# Rev_B.net
KiCad netlist of a schematic drawn in EAGLE
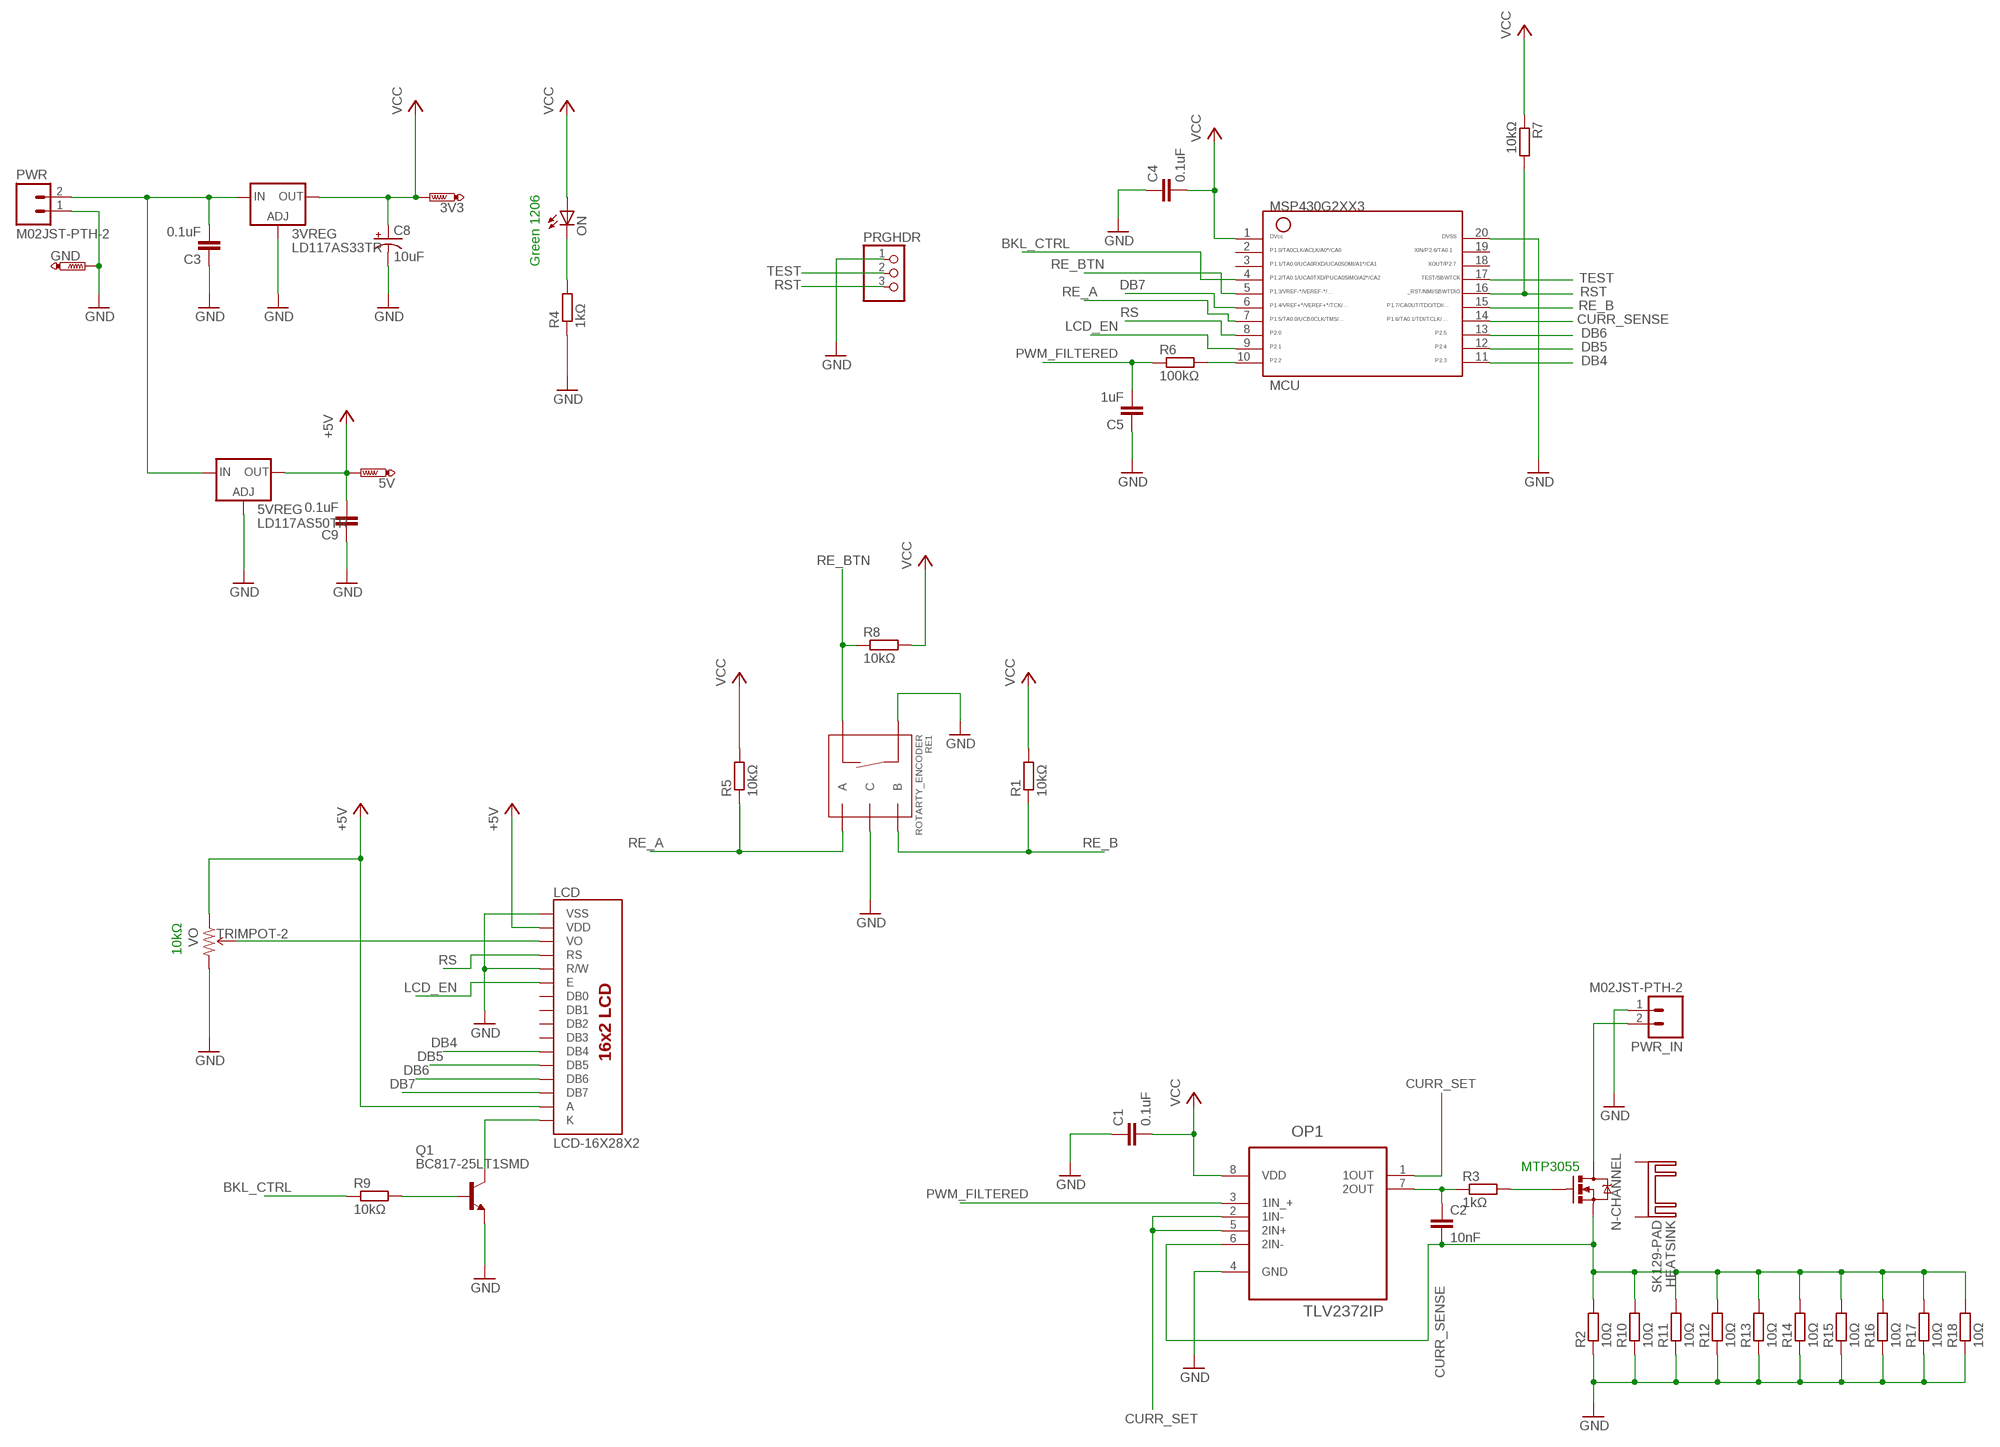
[diagram p0: schematic, sheet 1]

(export (version "E")
  (design (tool "Eeschema 10.0.6"))
  (components
    (comp (ref "3V3")
      (value "PTR1TP10SQ")
      (footprint "eagle-import:TP10SQ")
      (libsource (lib "eagle-import") (part "PTR1TP10SQ"))
    )
    (comp (ref "3VREG")
      (value "LD117AS33TR")
      (footprint "eagle-import:SOT223")
      (libsource (lib "eagle-import") (part "LD117A?S33TR"))
    )
    (comp (ref "5V")
      (value "PTR1TP10SQ")
      (footprint "eagle-import:TP10SQ")
      (libsource (lib "eagle-import") (part "PTR1TP10SQ"))
    )
    (comp (ref "5VREG")
      (value "LD117AS50TR")
      (footprint "eagle-import:SOT223")
      (libsource (lib "eagle-import") (part "LD117A?S50TR"))
    )
    (comp (ref "C1")
      (value "0.1uF")
      (footprint "eagle-import:C0805")
      (libsource (lib "eagle-import") (part "C-EUC0805"))
    )
    (comp (ref "C2")
      (value "10nF")
      (footprint "eagle-import:C0805")
      (libsource (lib "eagle-import") (part "C-EUC0805"))
    )
    (comp (ref "C3")
      (value "0.1uF")
      (footprint "eagle-import:C0805")
      (libsource (lib "eagle-import") (part "C-EUC0805"))
    )
    (comp (ref "C4")
      (value "0.1uF")
      (footprint "eagle-import:C0805")
      (libsource (lib "eagle-import") (part "C-EUC0805"))
    )
    (comp (ref "C5")
      (value "1uF")
      (footprint "eagle-import:C0805")
      (libsource (lib "eagle-import") (part "C-EUC0805"))
    )
    (comp (ref "C8")
      (value "10uF")
      (footprint "eagle-import:EIA3216")
      (libsource (lib "eagle-import") (part "CAP_POL1206"))
    )
    (comp (ref "C9")
      (value "0.1uF")
      (footprint "eagle-import:C0805")
      (libsource (lib "eagle-import") (part "C-EUC0805"))
    )
    (comp (ref "GND")
      (value "PTR1TP10SQ")
      (footprint "eagle-import:TP10SQ")
      (libsource (lib "eagle-import") (part "PTR1TP10SQ"))
    )
    (comp (ref "HEATSINK")
      (value "SK129-PAD")
      (footprint "eagle-import:SK129")
      (libsource (lib "eagle-import") (part "SK129-PAD"))
    )
    (comp (ref "LCD")
      (value "LCD-16X28X2")
      (footprint "eagle-import:LCD-8X2")
      (libsource (lib "eagle-import") (part "LCD-16X28X2"))
    )
    (comp (ref "MCU")
      (value "G2XX3---N20")
      (footprint "eagle-import:N20")
      (libsource (lib "eagle-import") (part "G2XX3---N20"))
    )
    (comp (ref "N-CHANNEL")
      (value "MOSFET-NCHANNELFQP30N06L")
      (footprint "eagle-import:TO220V")
      (libsource (lib "eagle-import") (part "MOSFET-NCHANNELFQP30N06L"))
    )
    (comp (ref "ON")
      (value "LEDCHIPLED_1206")
      (footprint "eagle-import:CHIPLED_1206")
      (libsource (lib "eagle-import") (part "LEDCHIPLED_1206"))
    )
    (comp (ref "OP1")
      (value "TLV2372IP")
      (footprint "eagle-import:DIP254P762X508-8")
      (libsource (lib "eagle-import") (part "TLV2372IP"))
    )
    (comp (ref "PRGHDR")
      (value "PINHD-1X3")
      (footprint "eagle-import:1X03")
      (libsource (lib "eagle-import") (part "PINHD-1X3"))
    )
    (comp (ref "PWR")
      (value "M02JST-PTH-2")
      (footprint "eagle-import:JST-2-PTH")
      (libsource (lib "eagle-import") (part "M02JST-PTH-2"))
    )
    (comp (ref "PWR_IN")
      (value "M02JST-PTH-2")
      (footprint "eagle-import:JST-2-PTH")
      (libsource (lib "eagle-import") (part "M02JST-PTH-2"))
    )
    (comp (ref "Q1")
      (value "BC817-25LT1SMD")
      (footprint "eagle-import:SOT23-BEC")
      (libsource (lib "eagle-import") (part "BC817SMD-25LT1"))
    )
    (comp (ref "R1")
      (value "10kΩ")
      (footprint "eagle-import:R0805")
      (libsource (lib "eagle-import") (part "R-EU_R0805"))
    )
    (comp (ref "R2")
      (value "10Ω")
      (footprint "eagle-import:R2512")
      (libsource (lib "eagle-import") (part "R-EU_R2512"))
    )
    (comp (ref "R3")
      (value "1kΩ")
      (footprint "eagle-import:R0805")
      (libsource (lib "eagle-import") (part "R-EU_R0805"))
    )
    (comp (ref "R4")
      (value "1kΩ")
      (footprint "eagle-import:R0805")
      (libsource (lib "eagle-import") (part "R-EU_R0805"))
    )
    (comp (ref "R5")
      (value "10kΩ")
      (footprint "eagle-import:R0805")
      (libsource (lib "eagle-import") (part "R-EU_R0805"))
    )
    (comp (ref "R6")
      (value "100kΩ")
      (footprint "eagle-import:R0805")
      (libsource (lib "eagle-import") (part "R-EU_R0805"))
    )
    (comp (ref "R7")
      (value "10kΩ")
      (footprint "eagle-import:R0805")
      (libsource (lib "eagle-import") (part "resistor_R-EU_R0805"))
    )
    (comp (ref "R8")
      (value "10kΩ")
      (footprint "eagle-import:R0805")
      (libsource (lib "eagle-import") (part "R-EU_R0805"))
    )
    (comp (ref "R9")
      (value "10kΩ")
      (footprint "eagle-import:R0805")
      (libsource (lib "eagle-import") (part "R-EU_R0805"))
    )
    (comp (ref "R10")
      (value "10Ω")
      (footprint "eagle-import:R2512")
      (libsource (lib "eagle-import") (part "R-EU_R2512"))
    )
    (comp (ref "R11")
      (value "10Ω")
      (footprint "eagle-import:R2512")
      (libsource (lib "eagle-import") (part "R-EU_R2512"))
    )
    (comp (ref "R12")
      (value "10Ω")
      (footprint "eagle-import:R2512")
      (libsource (lib "eagle-import") (part "R-EU_R2512"))
    )
    (comp (ref "R13")
      (value "10Ω")
      (footprint "eagle-import:R2512")
      (libsource (lib "eagle-import") (part "R-EU_R2512"))
    )
    (comp (ref "R14")
      (value "10Ω")
      (footprint "eagle-import:R2512")
      (libsource (lib "eagle-import") (part "R-EU_R2512"))
    )
    (comp (ref "R15")
      (value "10Ω")
      (footprint "eagle-import:R2512")
      (libsource (lib "eagle-import") (part "R-EU_R2512"))
    )
    (comp (ref "R16")
      (value "10Ω")
      (footprint "eagle-import:R2512")
      (libsource (lib "eagle-import") (part "R-EU_R2512"))
    )
    (comp (ref "R17")
      (value "10Ω")
      (footprint "eagle-import:R2512")
      (libsource (lib "eagle-import") (part "R-EU_R2512"))
    )
    (comp (ref "R18")
      (value "10Ω")
      (footprint "eagle-import:R2512")
      (libsource (lib "eagle-import") (part "R-EU_R2512"))
    )
    (comp (ref "RE1")
      (value "ROTARTY_ENCODER")
      (footprint "eagle-import:ROTARY_ENC_PLAIN")
      (libsource (lib "eagle-import") (part "ROTARTY_ENCODER"))
    )
    (comp (ref "VO")
      (value "TRIMPOT-2")
      (footprint "eagle-import:TRIMPOT_TC33")
      (libsource (lib "eagle-import") (part "TRIMPOT-2"))
    )
  )
  (nets
    (net (code "1") (name "+5V") (class "Default")
      (node (ref "5V") (pin "TP") (pinfunction "TP_TP") (pintype "input"))
      (node (ref "5VREG") (pin "4") (pinfunction "OUT_4") (pintype "passive"))
      (node (ref "C9") (pin "2") (pinfunction "2_2") (pintype "passive"))
      (node (ref "LCD") (pin "15") (pinfunction "A_15") (pintype "power_in"))
      (node (ref "LCD") (pin "2") (pinfunction "VDD_2") (pintype "power_in"))
      (node (ref "VO") (pin "1") (pinfunction "CCW_1") (pintype "passive"))
    )
    (net (code "2") (name "/BKL_CTRL") (class "Default")
      (node (ref "MCU") (pin "4") (pinfunction "4_4") (pintype "bidirectional"))
      (node (ref "R9") (pin "1") (pinfunction "1_1") (pintype "passive"))
    )
    (net (code "3") (name "/CURR_SENSE") (class "Default")
      (node (ref "C2") (pin "2") (pinfunction "2_2") (pintype "passive"))
      (node (ref "MCU") (pin "14") (pinfunction "14_14") (pintype "bidirectional"))
      (node (ref "N-CHANNEL") (pin "3") (pinfunction "S_3") (pintype "passive"))
      (node (ref "OP1") (pin "6") (pinfunction "2IN-_6") (pintype "input"))
      (node (ref "R10") (pin "2") (pinfunction "2_2") (pintype "passive"))
      (node (ref "R11") (pin "2") (pinfunction "2_2") (pintype "passive"))
      (node (ref "R12") (pin "2") (pinfunction "2_2") (pintype "passive"))
      (node (ref "R13") (pin "2") (pinfunction "2_2") (pintype "passive"))
      (node (ref "R14") (pin "2") (pinfunction "2_2") (pintype "passive"))
      (node (ref "R15") (pin "2") (pinfunction "2_2") (pintype "passive"))
      (node (ref "R16") (pin "2") (pinfunction "2_2") (pintype "passive"))
      (node (ref "R17") (pin "2") (pinfunction "2_2") (pintype "passive"))
      (node (ref "R18") (pin "2") (pinfunction "2_2") (pintype "passive"))
      (node (ref "R2") (pin "2") (pinfunction "2_2") (pintype "passive"))
    )
    (net (code "4") (name "/CURR_SET") (class "Default")
      (node (ref "OP1") (pin "1") (pinfunction "1OUT_1") (pintype "output"))
      (node (ref "OP1") (pin "2") (pinfunction "1IN-_2") (pintype "input"))
      (node (ref "OP1") (pin "5") (pinfunction "2IN+_5") (pintype "input"))
    )
    (net (code "5") (name "/DB4") (class "Default")
      (node (ref "LCD") (pin "11") (pinfunction "DB4_11") (pintype "bidirectional"))
      (node (ref "MCU") (pin "11") (pinfunction "11_11") (pintype "bidirectional"))
    )
    (net (code "6") (name "/DB5") (class "Default")
      (node (ref "LCD") (pin "12") (pinfunction "DB5_12") (pintype "bidirectional"))
      (node (ref "MCU") (pin "12") (pinfunction "12_12") (pintype "bidirectional"))
    )
    (net (code "7") (name "/DB6") (class "Default")
      (node (ref "LCD") (pin "13") (pinfunction "DB6_13") (pintype "bidirectional"))
      (node (ref "MCU") (pin "13") (pinfunction "13_13") (pintype "bidirectional"))
    )
    (net (code "8") (name "/DB7") (class "Default")
      (node (ref "LCD") (pin "14") (pinfunction "DB7_14") (pintype "bidirectional"))
      (node (ref "MCU") (pin "6") (pinfunction "6_6") (pintype "bidirectional"))
    )
    (net (code "9") (name "/LCD_EN") (class "Default")
      (node (ref "LCD") (pin "6") (pinfunction "E_6") (pintype "input"))
      (node (ref "MCU") (pin "9") (pinfunction "9_9") (pintype "bidirectional"))
    )
    (net (code "10") (name "/PWM_FILTERED") (class "Default")
      (node (ref "C5") (pin "2") (pinfunction "2_2") (pintype "passive"))
      (node (ref "OP1") (pin "3") (pinfunction "1IN_+_3") (pintype "input"))
      (node (ref "R6") (pin "1") (pinfunction "1_1") (pintype "passive"))
    )
    (net (code "11") (name "/RE_A") (class "Default")
      (node (ref "MCU") (pin "7") (pinfunction "7_7") (pintype "bidirectional"))
      (node (ref "R5") (pin "1") (pinfunction "1_1") (pintype "passive"))
      (node (ref "RE1") (pin "A") (pinfunction "A_A") (pintype "bidirectional"))
    )
    (net (code "12") (name "/RE_B") (class "Default")
      (node (ref "MCU") (pin "15") (pinfunction "15_15") (pintype "bidirectional"))
      (node (ref "R1") (pin "1") (pinfunction "1_1") (pintype "passive"))
      (node (ref "RE1") (pin "B") (pinfunction "B_B") (pintype "bidirectional"))
    )
    (net (code "13") (name "/RE_BTN") (class "Default")
      (node (ref "MCU") (pin "5") (pinfunction "5_5") (pintype "bidirectional"))
      (node (ref "R8") (pin "1") (pinfunction "1_1") (pintype "passive"))
      (node (ref "RE1") (pin "SW-") (pinfunction "SW-_SW-") (pintype "bidirectional"))
    )
    (net (code "14") (name "/RS") (class "Default")
      (node (ref "LCD") (pin "4") (pinfunction "RS_4") (pintype "input"))
      (node (ref "MCU") (pin "8") (pinfunction "8_8") (pintype "bidirectional"))
    )
    (net (code "15") (name "/RST") (class "Default")
      (node (ref "MCU") (pin "16") (pinfunction "16_16") (pintype "bidirectional"))
      (node (ref "PRGHDR") (pin "3") (pinfunction "3_3") (pintype "passive"))
      (node (ref "R7") (pin "2") (pinfunction "2_2") (pintype "passive"))
    )
    (net (code "16") (name "/TEST") (class "Default")
      (node (ref "MCU") (pin "17") (pinfunction "17_17") (pintype "bidirectional"))
      (node (ref "PRGHDR") (pin "2") (pinfunction "2_2") (pintype "passive"))
    )
    (net (code "17") (name "GND") (class "Default")
      (node (ref "3VREG") (pin "1") (pinfunction "ADJ_1") (pintype "input"))
      (node (ref "5VREG") (pin "1") (pinfunction "ADJ_1") (pintype "input"))
      (node (ref "C1") (pin "1") (pinfunction "1_1") (pintype "passive"))
      (node (ref "C3") (pin "1") (pinfunction "1_1") (pintype "passive"))
      (node (ref "C4") (pin "1") (pinfunction "1_1") (pintype "passive"))
      (node (ref "C5") (pin "1") (pinfunction "1_1") (pintype "passive"))
      (node (ref "C8") (pin "C") (pinfunction "-_C") (pintype "passive"))
      (node (ref "C9") (pin "1") (pinfunction "1_1") (pintype "passive"))
      (node (ref "GND") (pin "TP") (pinfunction "TP_TP") (pintype "input"))
      (node (ref "LCD") (pin "1") (pinfunction "VSS_1") (pintype "power_in"))
      (node (ref "LCD") (pin "5") (pinfunction "R/W_5") (pintype "input"))
      (node (ref "MCU") (pin "20") (pinfunction "20_20") (pintype "bidirectional"))
      (node (ref "OP1") (pin "4") (pinfunction "GND_4") (pintype "passive"))
      (node (ref "PRGHDR") (pin "1") (pinfunction "1_1") (pintype "passive"))
      (node (ref "PWR") (pin "1") (pinfunction "1_1") (pintype "passive"))
      (node (ref "PWR_IN") (pin "1") (pinfunction "1_1") (pintype "passive"))
      (node (ref "Q1") (pin "E") (pinfunction "E_E") (pintype "passive"))
      (node (ref "R10") (pin "1") (pinfunction "1_1") (pintype "passive"))
      (node (ref "R11") (pin "1") (pinfunction "1_1") (pintype "passive"))
      (node (ref "R12") (pin "1") (pinfunction "1_1") (pintype "passive"))
      (node (ref "R13") (pin "1") (pinfunction "1_1") (pintype "passive"))
      (node (ref "R14") (pin "1") (pinfunction "1_1") (pintype "passive"))
      (node (ref "R15") (pin "1") (pinfunction "1_1") (pintype "passive"))
      (node (ref "R16") (pin "1") (pinfunction "1_1") (pintype "passive"))
      (node (ref "R17") (pin "1") (pinfunction "1_1") (pintype "passive"))
      (node (ref "R18") (pin "1") (pinfunction "1_1") (pintype "passive"))
      (node (ref "R2") (pin "1") (pinfunction "1_1") (pintype "passive"))
      (node (ref "R4") (pin "1") (pinfunction "1_1") (pintype "passive"))
      (node (ref "RE1") (pin "C") (pinfunction "C_C") (pintype "bidirectional"))
      (node (ref "RE1") (pin "SW+") (pinfunction "SW+_SW+") (pintype "bidirectional"))
      (node (ref "VO") (pin "3") (pinfunction "CW_3") (pintype "passive"))
    )
    (net (code "18") (name "Net-(3VREG-IN)") (class "Default")
      (node (ref "3VREG") (pin "3") (pinfunction "IN_3") (pintype "input"))
      (node (ref "5VREG") (pin "3") (pinfunction "IN_3") (pintype "input"))
      (node (ref "C3") (pin "2") (pinfunction "2_2") (pintype "passive"))
      (node (ref "PWR") (pin "2") (pinfunction "2_2") (pintype "passive"))
    )
    (net (code "19") (name "Net-(LCD-K)") (class "Default")
      (node (ref "LCD") (pin "16") (pinfunction "K_16") (pintype "power_in"))
      (node (ref "Q1") (pin "C") (pinfunction "C_C") (pintype "passive"))
    )
    (net (code "20") (name "Net-(LCD-VO)") (class "Default")
      (node (ref "LCD") (pin "3") (pinfunction "VO_3") (pintype "bidirectional"))
      (node (ref "VO") (pin "2") (pinfunction "WIPER_2") (pintype "passive"))
    )
    (net (code "21") (name "Net-(MCU-Pad10)") (class "Default")
      (node (ref "MCU") (pin "10") (pinfunction "10_10") (pintype "bidirectional"))
      (node (ref "R6") (pin "2") (pinfunction "2_2") (pintype "passive"))
    )
    (net (code "22") (name "Net-(N-CHANNEL-D)") (class "Default")
      (node (ref "N-CHANNEL") (pin "2") (pinfunction "D_2") (pintype "passive"))
      (node (ref "PWR_IN") (pin "2") (pinfunction "2_2") (pintype "passive"))
    )
    (net (code "23") (name "Net-(N-CHANNEL-G)") (class "Default")
      (node (ref "N-CHANNEL") (pin "1") (pinfunction "G_1") (pintype "passive"))
      (node (ref "R3") (pin "2") (pinfunction "2_2") (pintype "passive"))
    )
    (net (code "24") (name "Net-(ON-PadC)") (class "Default")
      (node (ref "ON") (pin "C") (pinfunction "C_C") (pintype "passive"))
      (node (ref "R4") (pin "2") (pinfunction "2_2") (pintype "passive"))
    )
    (net (code "25") (name "Net-(OP1-2OUT)") (class "Default")
      (node (ref "C2") (pin "1") (pinfunction "1_1") (pintype "passive"))
      (node (ref "OP1") (pin "7") (pinfunction "2OUT_7") (pintype "output"))
      (node (ref "R3") (pin "1") (pinfunction "1_1") (pintype "passive"))
    )
    (net (code "26") (name "Net-(Q1-PadB)") (class "Default")
      (node (ref "Q1") (pin "B") (pinfunction "B_B") (pintype "passive"))
      (node (ref "R9") (pin "2") (pinfunction "2_2") (pintype "passive"))
    )
    (net (code "27") (name "VCC") (class "Default")
      (node (ref "3V3") (pin "TP") (pinfunction "TP_TP") (pintype "input"))
      (node (ref "3VREG") (pin "4") (pinfunction "OUT_4") (pintype "passive"))
      (node (ref "C1") (pin "2") (pinfunction "2_2") (pintype "passive"))
      (node (ref "C4") (pin "2") (pinfunction "2_2") (pintype "passive"))
      (node (ref "C8") (pin "A") (pinfunction "+_A") (pintype "passive"))
      (node (ref "MCU") (pin "1") (pinfunction "1_1") (pintype "bidirectional"))
      (node (ref "ON") (pin "A") (pinfunction "A_A") (pintype "passive"))
      (node (ref "OP1") (pin "8") (pinfunction "VDD_8") (pintype "power_in"))
      (node (ref "R1") (pin "2") (pinfunction "2_2") (pintype "passive"))
      (node (ref "R5") (pin "2") (pinfunction "2_2") (pintype "passive"))
      (node (ref "R7") (pin "1") (pinfunction "1_1") (pintype "passive"))
      (node (ref "R8") (pin "2") (pinfunction "2_2") (pintype "passive"))
    )
    (net (code "28") (name "unconnected-(HEATSINK-K-PadA2,5)") (class "Default")
      (node (ref "HEATSINK") (pin "A2,5") (pinfunction "K_A2,5") (pintype "passive"))
    )
    (net (code "29") (name "unconnected-(HEATSINK-K-PadB2,5)") (class "Default")
      (node (ref "HEATSINK") (pin "B2,5") (pinfunction "K_B2,5") (pintype "passive"))
    )
    (net (code "30") (name "unconnected-(LCD-DB0-Pad7)") (class "Default")
      (node (ref "LCD") (pin "7") (pinfunction "DB0_7") (pintype "bidirectional"))
    )
    (net (code "31") (name "unconnected-(LCD-DB1-Pad8)") (class "Default")
      (node (ref "LCD") (pin "8") (pinfunction "DB1_8") (pintype "bidirectional"))
    )
    (net (code "32") (name "unconnected-(LCD-DB2-Pad9)") (class "Default")
      (node (ref "LCD") (pin "9") (pinfunction "DB2_9") (pintype "bidirectional"))
    )
    (net (code "33") (name "unconnected-(LCD-DB3-Pad10)") (class "Default")
      (node (ref "LCD") (pin "10") (pinfunction "DB3_10") (pintype "bidirectional"))
    )
    (net (code "34") (name "unconnected-(MCU-Pad2)") (class "Default")
      (node (ref "MCU") (pin "2") (pinfunction "2_2") (pintype "bidirectional"))
    )
    (net (code "35") (name "unconnected-(MCU-Pad3)") (class "Default")
      (node (ref "MCU") (pin "3") (pinfunction "3_3") (pintype "bidirectional"))
    )
    (net (code "36") (name "unconnected-(MCU-Pad18)") (class "Default")
      (node (ref "MCU") (pin "18") (pinfunction "18_18") (pintype "bidirectional"))
    )
    (net (code "37") (name "unconnected-(MCU-Pad19)") (class "Default")
      (node (ref "MCU") (pin "19") (pinfunction "19_19") (pintype "bidirectional"))
    )
  )
)
